# Isolator.net
KiCad netlist of a schematic drawn in EAGLE
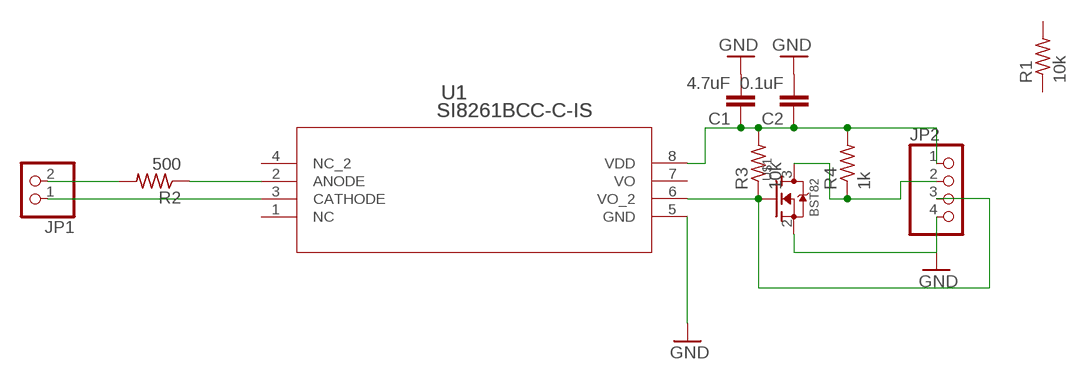
[diagram p0: schematic, sheet 1]

(export (version "E")
  (design (tool "Eeschema 10.0.6"))
  (components
    (comp (ref "C1")
      (value "4.7uF")
      (footprint "eagle-import:C0402")
      (libsource (lib "eagle-import") (part "C-EUC0402"))
    )
    (comp (ref "C2")
      (value "0.1uF")
      (footprint "eagle-import:C0402")
      (libsource (lib "eagle-import") (part "C-EUC0402"))
    )
    (comp (ref "JP1")
      (value "PINHD-1X2")
      (footprint "eagle-import:1X02")
      (libsource (lib "eagle-import") (part "PINHD-1X2"))
    )
    (comp (ref "JP2")
      (value "PINHD-1X4")
      (footprint "eagle-import:1X04")
      (libsource (lib "eagle-import") (part "PINHD-1X4"))
    )
    (comp (ref "R1")
      (value "10k")
      (footprint "eagle-import:R0402")
      (libsource (lib "eagle-import") (part "R-US_R0402"))
    )
    (comp (ref "R2")
      (value "500")
      (footprint "eagle-import:R0402")
      (libsource (lib "eagle-import") (part "R-US_R0402"))
    )
    (comp (ref "R3")
      (value "10k")
      (footprint "eagle-import:R0402")
      (libsource (lib "eagle-import") (part "R-US_R0402"))
    )
    (comp (ref "R4")
      (value "1k")
      (footprint "eagle-import:R0402")
      (libsource (lib "eagle-import") (part "R-US_R0402"))
    )
    (comp (ref "U$1")
      (value "BST82")
      (footprint "eagle-import:SOT23-3")
      (libsource (lib "eagle-import") (part "BST82"))
    )
    (comp (ref "U1")
      (value "SI8261BCC-C-IS")
      (footprint "eagle-import:SOIC_8_127MM")
      (libsource (lib "eagle-import") (part "SI8261BCC-C-IS"))
    )
  )
  (nets
    (net (code "1") (name "GND") (class "Default")
      (node (ref "C1") (pin "2") (pinfunction "2_2") (pintype "passive"))
      (node (ref "C2") (pin "2") (pinfunction "2_2") (pintype "passive"))
      (node (ref "JP2") (pin "4") (pinfunction "4_4") (pintype "passive"))
      (node (ref "U$1") (pin "2") (pinfunction "S_2") (pintype "bidirectional"))
      (node (ref "U1") (pin "5") (pinfunction "GND_5") (pintype "power_in"))
    )
    (net (code "2") (name "Net-(JP1-Pad2)") (class "Default")
      (node (ref "JP1") (pin "2") (pinfunction "2_2") (pintype "passive"))
      (node (ref "R2") (pin "2") (pinfunction "2_2") (pintype "passive"))
    )
    (net (code "3") (name "Net-(U$1-D)") (class "Default")
      (node (ref "JP2") (pin "2") (pinfunction "2_2") (pintype "passive"))
      (node (ref "R4") (pin "1") (pinfunction "1_1") (pintype "passive"))
      (node (ref "U$1") (pin "3") (pinfunction "D_3") (pintype "bidirectional"))
    )
    (net (code "4") (name "Net-(U$1-G)") (class "Default")
      (node (ref "JP2") (pin "3") (pinfunction "3_3") (pintype "passive"))
      (node (ref "R3") (pin "1") (pinfunction "1_1") (pintype "passive"))
      (node (ref "U$1") (pin "1") (pinfunction "G_1") (pintype "bidirectional"))
      (node (ref "U1") (pin "6") (pinfunction "VO_2_6") (pintype "output"))
    )
    (net (code "5") (name "Net-(U1-ANODE)") (class "Default")
      (node (ref "R2") (pin "1") (pinfunction "1_1") (pintype "passive"))
      (node (ref "U1") (pin "2") (pinfunction "ANODE_2") (pintype "passive"))
    )
    (net (code "6") (name "Net-(U1-CATHODE)") (class "Default")
      (node (ref "JP1") (pin "1") (pinfunction "1_1") (pintype "passive"))
      (node (ref "U1") (pin "3") (pinfunction "CATHODE_3") (pintype "passive"))
    )
    (net (code "7") (name "Net-(U1-VDD)") (class "Default")
      (node (ref "C1") (pin "1") (pinfunction "1_1") (pintype "passive"))
      (node (ref "C2") (pin "1") (pinfunction "1_1") (pintype "passive"))
      (node (ref "JP2") (pin "1") (pinfunction "1_1") (pintype "passive"))
      (node (ref "R3") (pin "2") (pinfunction "2_2") (pintype "passive"))
      (node (ref "R4") (pin "2") (pinfunction "2_2") (pintype "passive"))
      (node (ref "U1") (pin "8") (pinfunction "VDD_8") (pintype "power_in"))
    )
    (net (code "8") (name "unconnected-(R1-Pad1)") (class "Default")
      (node (ref "R1") (pin "1") (pinfunction "1_1") (pintype "passive"))
    )
    (net (code "9") (name "unconnected-(R1-Pad2)") (class "Default")
      (node (ref "R1") (pin "2") (pinfunction "2_2") (pintype "passive"))
    )
    (net (code "10") (name "unconnected-(U1-NC-Pad1)") (class "Default")
      (node (ref "U1") (pin "1") (pinfunction "NC_1") (pintype "no_connect"))
    )
    (net (code "11") (name "unconnected-(U1-NC_2-Pad4)") (class "Default")
      (node (ref "U1") (pin "4") (pinfunction "NC_2_4") (pintype "no_connect"))
    )
    (net (code "12") (name "unconnected-(U1-VO-Pad7)") (class "Default")
      (node (ref "U1") (pin "7") (pinfunction "VO_7") (pintype "output"))
    )
  )
)
